# SCH_Boom-Crane-Controller_2025-03-01.net
KiCad netlist of a schematic drawn in EasyEDA
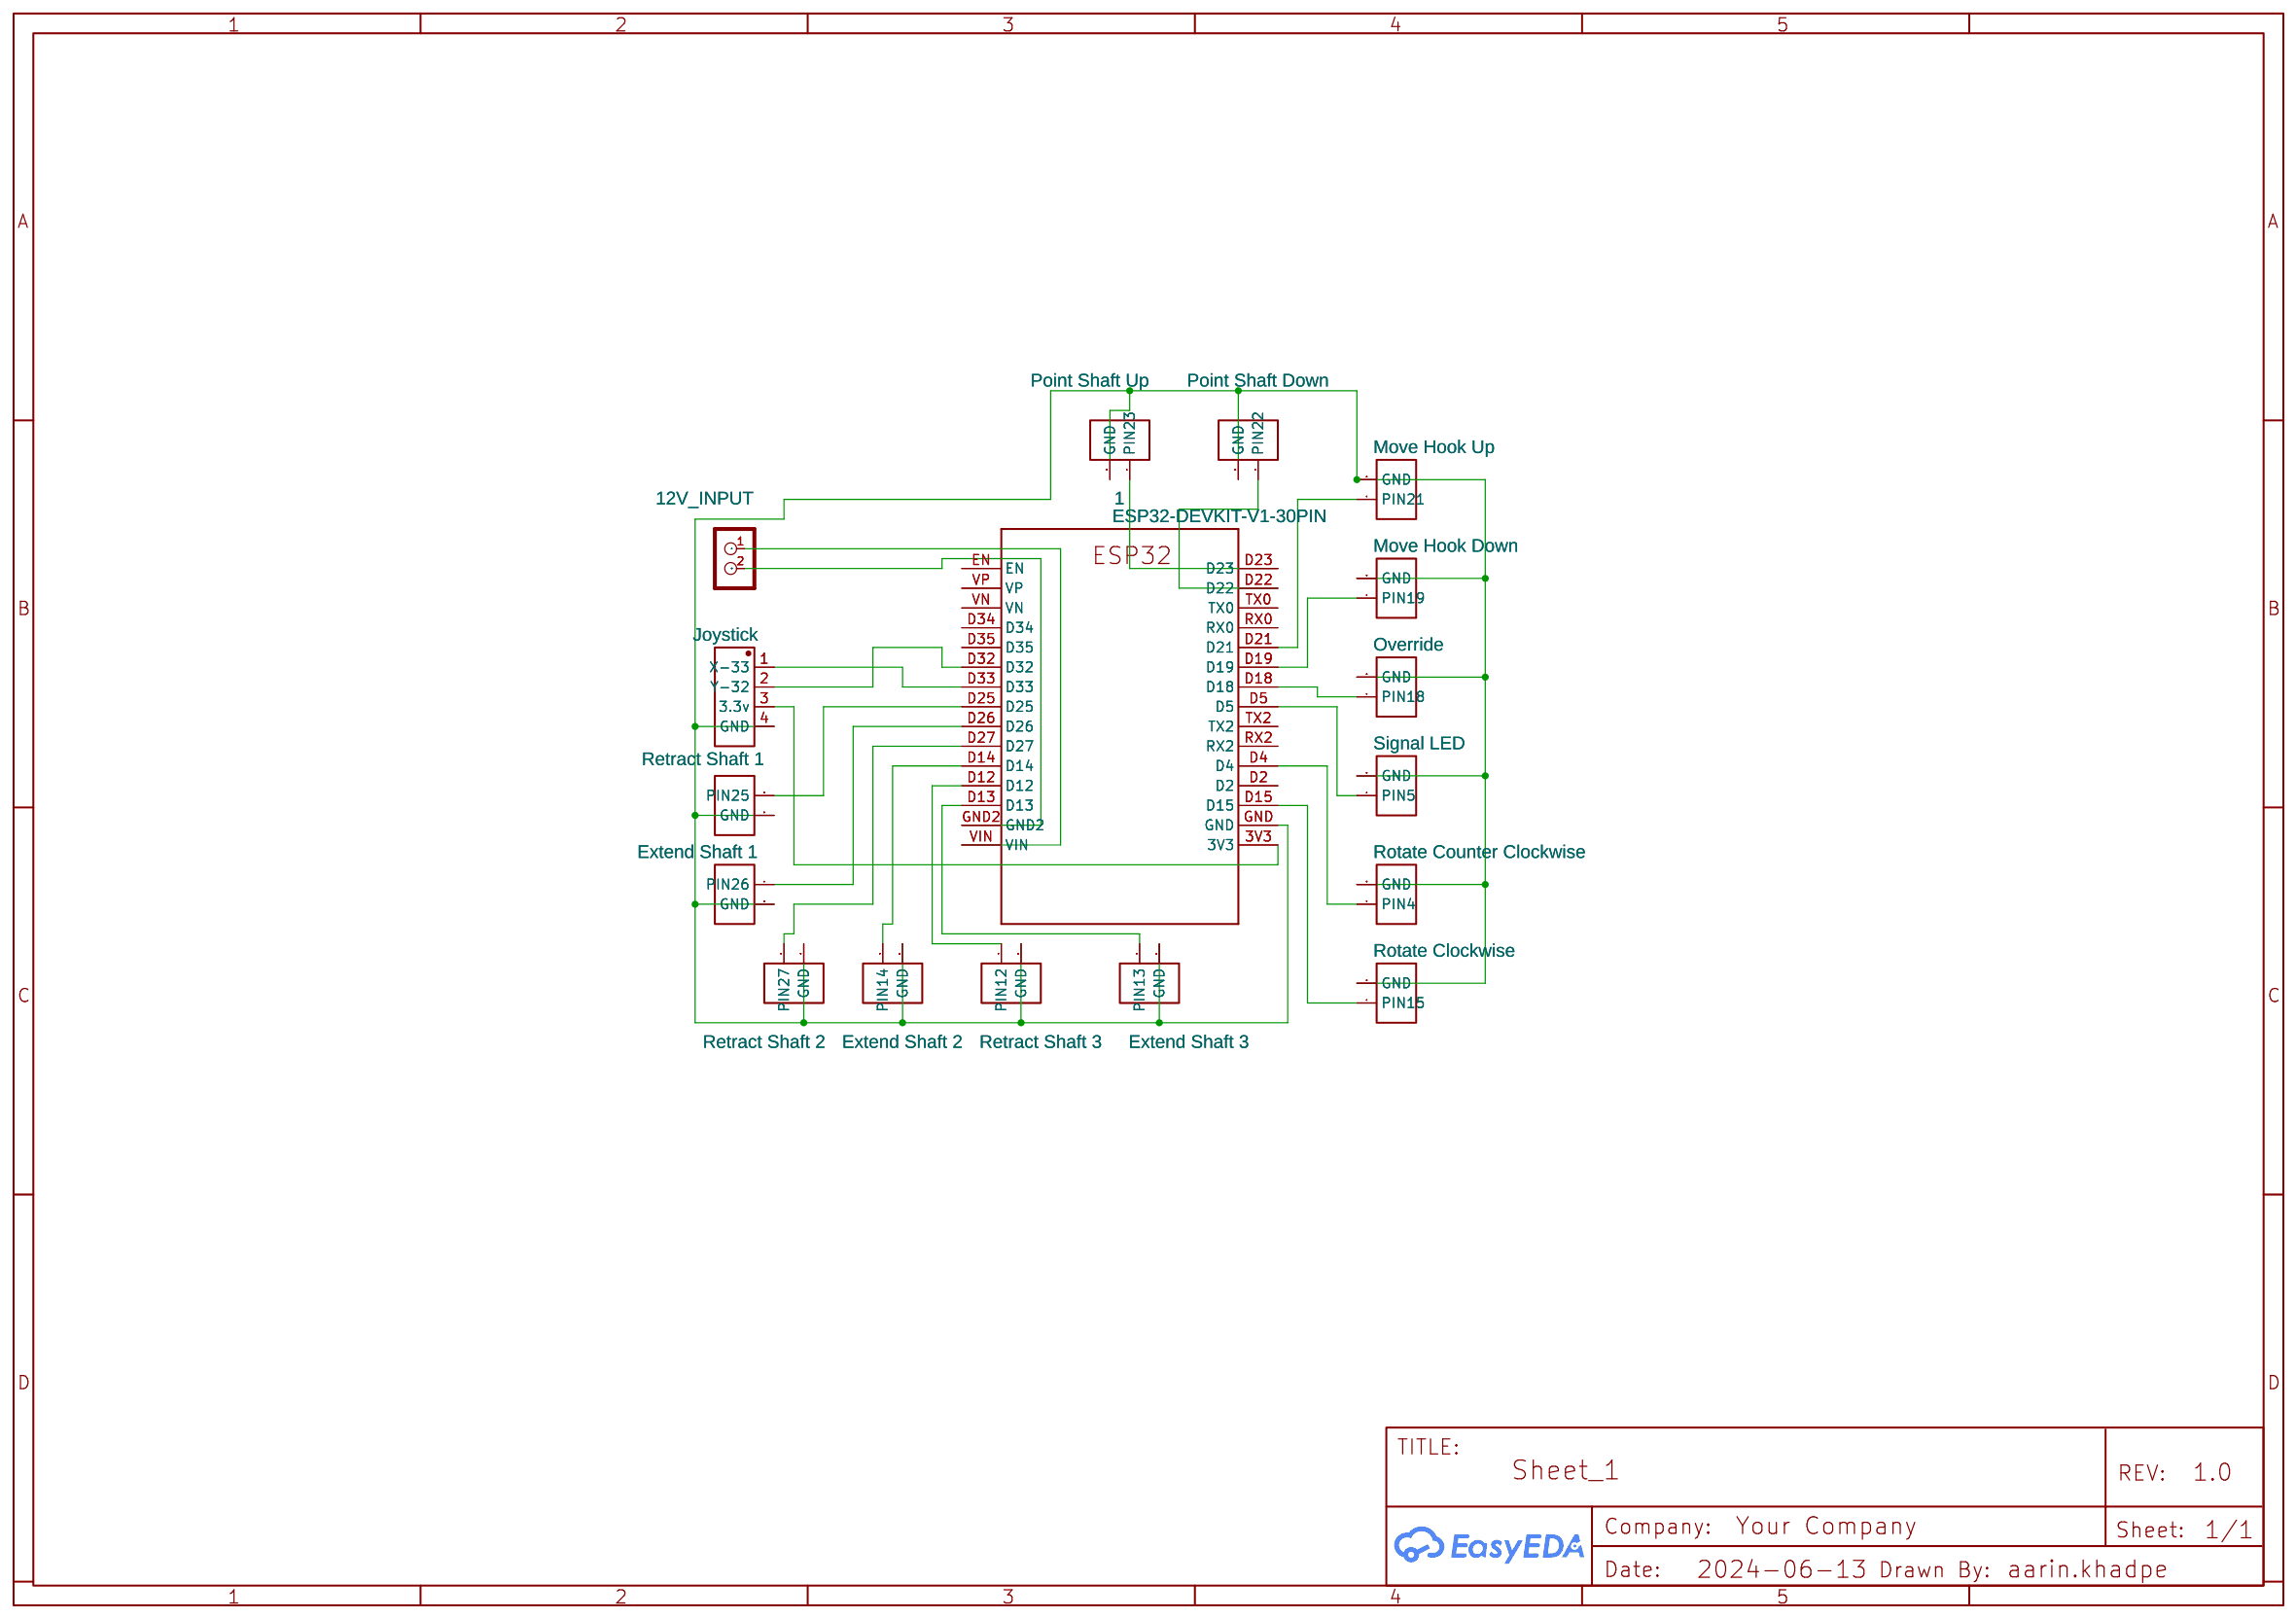
[diagram p0: schematic sheet]

(export (version "E")
  (design (tool "Eeschema 10.0.6"))
  (components
    (comp (ref "1") (value "ESP32-DEVKIT-V1-30PIN") (libsource (lib "") (part "ESP32-DEVKIT-V1-30PIN")))
    (comp (ref "12V_INPUT")
      (value "CON_TERMINAL_BLOCK_02-5MM")
      (libsource (lib "") (part "CON_TERMINAL_BLOCK_02-5MM"))
    )
    (comp (ref "H1")
      (value "Joystick")
      (fields (field (name "Manufacturer Part") "排针 1*4P"))
      (libsource (lib "") (part "Header-Male-2.54_1x4_C59481"))
    )
    (comp (ref "P1")
      (value "Extend Shaft 1")
      (fields (field (name "Manufacturer Part") "2.54-1*2P母") (field (name "Manufacturer") "BOOMELE(博穆精密)"))
      (libsource (lib "") (part "Header-Female-2.54_1x2_5"))
    )
    (comp (ref "P2")
      (value "Retract Shaft 1")
      (fields (field (name "Manufacturer Part") "2.54-1*2P母") (field (name "Manufacturer") "BOOMELE(博穆精密)"))
      (libsource (lib "") (part "Header-Female-2.54_1x2_1"))
    )
    (comp (ref "P3")
      (value "Extend Shaft 2")
      (fields (field (name "Manufacturer Part") "2.54-1*2P母") (field (name "Manufacturer") "BOOMELE(博穆精密)"))
      (libsource (lib "") (part "Header-Female-2.54_1x2_11"))
    )
    (comp (ref "P4")
      (value "Retract Shaft 2")
      (fields (field (name "Manufacturer Part") "2.54-1*2P母") (field (name "Manufacturer") "BOOMELE(博穆精密)"))
      (libsource (lib "") (part "Header-Female-2.54_1x2"))
    )
    (comp (ref "P5")
      (value "Retract Shaft 3")
      (fields (field (name "Manufacturer Part") "2.54-1*2P母") (field (name "Manufacturer") "BOOMELE(博穆精密)"))
      (libsource (lib "") (part "Header-Female-2.54_1x2_6"))
    )
    (comp (ref "P6")
      (value "Extend Shaft 3")
      (fields (field (name "Manufacturer Part") "2.54-1*2P母") (field (name "Manufacturer") "BOOMELE(博穆精密)"))
      (libsource (lib "") (part "Header-Female-2.54_1x2_13"))
    )
    (comp (ref "P7")
      (value "Point Shaft Up")
      (fields (field (name "Manufacturer Part") "2.54-1*2P母") (field (name "Manufacturer") "BOOMELE(博穆精密)"))
      (libsource (lib "") (part "Header-Female-2.54_1x2_8"))
    )
    (comp (ref "P8")
      (value "Point Shaft Down")
      (fields (field (name "Manufacturer Part") "2.54-1*2P母") (field (name "Manufacturer") "BOOMELE(博穆精密)"))
      (libsource (lib "") (part "Header-Female-2.54_1x2_10"))
    )
    (comp (ref "P9")
      (value "Move Hook Down")
      (fields (field (name "Manufacturer Part") "2.54-1*2P母") (field (name "Manufacturer") "BOOMELE(博穆精密)"))
      (libsource (lib "") (part "Header-Female-2.54_1x2_9"))
    )
    (comp (ref "P10")
      (value "Move Hook Up")
      (fields (field (name "Manufacturer Part") "2.54-1*2P母") (field (name "Manufacturer") "BOOMELE(博穆精密)"))
      (libsource (lib "") (part "Header-Female-2.54_1x2_3"))
    )
    (comp (ref "P11")
      (value "Rotate Clockwise")
      (fields (field (name "Manufacturer Part") "2.54-1*2P母") (field (name "Manufacturer") "BOOMELE(博穆精密)"))
      (libsource (lib "") (part "Header-Female-2.54_1x2_12"))
    )
    (comp (ref "P12")
      (value "Rotate Counter Clockwise")
      (fields (field (name "Manufacturer Part") "2.54-1*2P母") (field (name "Manufacturer") "BOOMELE(博穆精密)"))
      (libsource (lib "") (part "Header-Female-2.54_1x2_2"))
    )
    (comp (ref "P13")
      (value "Override")
      (fields (field (name "Manufacturer Part") "2.54-1*2P母") (field (name "Manufacturer") "BOOMELE(博穆精密)"))
      (libsource (lib "") (part "Header-Female-2.54_1x2_7"))
    )
    (comp (ref "P14")
      (value "Signal LED")
      (fields (field (name "Manufacturer Part") "2.54-1*2P母") (field (name "Manufacturer") "BOOMELE(博穆精密)"))
      (libsource (lib "") (part "Header-Female-2.54_1x2_4"))
    )
  )
  (nets
    (net (code "1") (name "Net-(1-PadGND2)") (class "Default")
      (node (ref "1") (pin "GND2") (pinfunction "GND2_GND2") (pintype "unspecified"))
      (node (ref "12V_INPUT") (pin "2") (pinfunction "2_2") (pintype "unspecified"))
    )
    (net (code "2") (name "Net-(1-PadVIN)") (class "Default")
      (node (ref "1") (pin "VIN") (pinfunction "VIN_VIN") (pintype "unspecified"))
      (node (ref "12V_INPUT") (pin "1") (pinfunction "1_1") (pintype "unspecified"))
    )
    (net (code "3") (name "Net-(H1-3.3v)") (class "Default")
      (node (ref "1") (pin "3V3") (pinfunction "3V3_3V3") (pintype "unspecified"))
      (node (ref "H1") (pin "3") (pinfunction "3.3v_3") (pintype "unspecified"))
    )
    (net (code "4") (name "Net-(H1-GND)") (class "Default")
      (node (ref "1") (pin "GND") (pinfunction "GND_GND") (pintype "unspecified"))
      (node (ref "H1") (pin "4") (pinfunction "GND_4") (pintype "unspecified"))
      (node (ref "P1") (pin "2") (pinfunction "GND_2") (pintype "input"))
      (node (ref "P10") (pin "2") (pinfunction "GND_2") (pintype "input"))
      (node (ref "P11") (pin "2") (pinfunction "GND_2") (pintype "input"))
      (node (ref "P12") (pin "2") (pinfunction "GND_2") (pintype "input"))
      (node (ref "P13") (pin "2") (pinfunction "GND_2") (pintype "input"))
      (node (ref "P14") (pin "2") (pinfunction "GND_2") (pintype "input"))
      (node (ref "P2") (pin "2") (pinfunction "GND_2") (pintype "input"))
      (node (ref "P3") (pin "2") (pinfunction "GND_2") (pintype "input"))
      (node (ref "P4") (pin "2") (pinfunction "GND_2") (pintype "input"))
      (node (ref "P5") (pin "2") (pinfunction "GND_2") (pintype "input"))
      (node (ref "P6") (pin "2") (pinfunction "GND_2") (pintype "input"))
      (node (ref "P7") (pin "2") (pinfunction "GND_2") (pintype "input"))
      (node (ref "P8") (pin "2") (pinfunction "GND_2") (pintype "input"))
      (node (ref "P9") (pin "2") (pinfunction "GND_2") (pintype "input"))
    )
    (net (code "5") (name "Net-(H1-X-33)") (class "Default")
      (node (ref "1") (pin "D33") (pinfunction "D33_D33") (pintype "unspecified"))
      (node (ref "H1") (pin "1") (pinfunction "X-33_1") (pintype "unspecified"))
    )
    (net (code "6") (name "Net-(H1-Y-32)") (class "Default")
      (node (ref "1") (pin "D32") (pinfunction "D32_D32") (pintype "unspecified"))
      (node (ref "H1") (pin "2") (pinfunction "Y-32_2") (pintype "unspecified"))
    )
    (net (code "7") (name "Net-(P1-PIN26)") (class "Default")
      (node (ref "1") (pin "D26") (pinfunction "D26_D26") (pintype "unspecified"))
      (node (ref "P1") (pin "1") (pinfunction "PIN26_1") (pintype "input"))
    )
    (net (code "8") (name "Net-(P2-PIN25)") (class "Default")
      (node (ref "1") (pin "D25") (pinfunction "D25_D25") (pintype "unspecified"))
      (node (ref "P2") (pin "1") (pinfunction "PIN25_1") (pintype "input"))
    )
    (net (code "9") (name "Net-(P3-PIN14)") (class "Default")
      (node (ref "1") (pin "D14") (pinfunction "D14_D14") (pintype "unspecified"))
      (node (ref "P3") (pin "1") (pinfunction "PIN14_1") (pintype "input"))
    )
    (net (code "10") (name "Net-(P4-PIN27)") (class "Default")
      (node (ref "1") (pin "D27") (pinfunction "D27_D27") (pintype "unspecified"))
      (node (ref "P4") (pin "1") (pinfunction "PIN27_1") (pintype "input"))
    )
    (net (code "11") (name "Net-(P5-PIN12)") (class "Default")
      (node (ref "1") (pin "D12") (pinfunction "D12_D12") (pintype "unspecified"))
      (node (ref "P5") (pin "1") (pinfunction "PIN12_1") (pintype "input"))
    )
    (net (code "12") (name "Net-(P6-PIN13)") (class "Default")
      (node (ref "1") (pin "D13") (pinfunction "D13_D13") (pintype "unspecified"))
      (node (ref "P6") (pin "1") (pinfunction "PIN13_1") (pintype "input"))
    )
    (net (code "13") (name "Net-(P7-PIN23)") (class "Default")
      (node (ref "1") (pin "D23") (pinfunction "D23_D23") (pintype "unspecified"))
      (node (ref "P7") (pin "1") (pinfunction "PIN23_1") (pintype "input"))
    )
    (net (code "14") (name "Net-(P8-PIN22)") (class "Default")
      (node (ref "1") (pin "D22") (pinfunction "D22_D22") (pintype "unspecified"))
      (node (ref "P8") (pin "1") (pinfunction "PIN22_1") (pintype "input"))
    )
    (net (code "15") (name "Net-(P9-PIN19)") (class "Default")
      (node (ref "1") (pin "D19") (pinfunction "D19_D19") (pintype "unspecified"))
      (node (ref "P9") (pin "1") (pinfunction "PIN19_1") (pintype "input"))
    )
    (net (code "16") (name "Net-(P10-PIN21)") (class "Default")
      (node (ref "1") (pin "D21") (pinfunction "D21_D21") (pintype "unspecified"))
      (node (ref "P10") (pin "1") (pinfunction "PIN21_1") (pintype "input"))
    )
    (net (code "17") (name "Net-(P11-PIN15)") (class "Default")
      (node (ref "1") (pin "D15") (pinfunction "D15_D15") (pintype "unspecified"))
      (node (ref "P11") (pin "1") (pinfunction "PIN15_1") (pintype "input"))
    )
    (net (code "18") (name "Net-(P12-PIN4)") (class "Default")
      (node (ref "1") (pin "D4") (pinfunction "D4_D4") (pintype "unspecified"))
      (node (ref "P12") (pin "1") (pinfunction "PIN4_1") (pintype "input"))
    )
    (net (code "19") (name "Net-(P13-PIN18)") (class "Default")
      (node (ref "1") (pin "D18") (pinfunction "D18_D18") (pintype "unspecified"))
      (node (ref "P13") (pin "1") (pinfunction "PIN18_1") (pintype "input"))
    )
    (net (code "20") (name "Net-(P14-PIN5)") (class "Default")
      (node (ref "1") (pin "D5") (pinfunction "D5_D5") (pintype "unspecified"))
      (node (ref "P14") (pin "1") (pinfunction "PIN5_1") (pintype "input"))
    )
    (net (code "21") (name "unconnected-(1-PadD2)") (class "Default")
      (node (ref "1") (pin "D2") (pinfunction "D2_D2") (pintype "unspecified"))
    )
    (net (code "22") (name "unconnected-(1-PadD34)") (class "Default")
      (node (ref "1") (pin "D34") (pinfunction "D34_D34") (pintype "unspecified"))
    )
    (net (code "23") (name "unconnected-(1-PadD35)") (class "Default")
      (node (ref "1") (pin "D35") (pinfunction "D35_D35") (pintype "unspecified"))
    )
    (net (code "24") (name "unconnected-(1-PadEN)") (class "Default")
      (node (ref "1") (pin "EN") (pinfunction "EN_EN") (pintype "unspecified"))
    )
    (net (code "25") (name "unconnected-(1-PadRX0)") (class "Default")
      (node (ref "1") (pin "RX0") (pinfunction "RX0_RX0") (pintype "unspecified"))
    )
    (net (code "26") (name "unconnected-(1-PadRX2)") (class "Default")
      (node (ref "1") (pin "RX2") (pinfunction "RX2_RX2") (pintype "unspecified"))
    )
    (net (code "27") (name "unconnected-(1-PadTX0)") (class "Default")
      (node (ref "1") (pin "TX0") (pinfunction "TX0_TX0") (pintype "unspecified"))
    )
    (net (code "28") (name "unconnected-(1-PadTX2)") (class "Default")
      (node (ref "1") (pin "TX2") (pinfunction "TX2_TX2") (pintype "unspecified"))
    )
    (net (code "29") (name "unconnected-(1-PadVN)") (class "Default")
      (node (ref "1") (pin "VN") (pinfunction "VN_VN") (pintype "unspecified"))
    )
    (net (code "30") (name "unconnected-(1-PadVP)") (class "Default")
      (node (ref "1") (pin "VP") (pinfunction "VP_VP") (pintype "unspecified"))
    )
  )
)
